# FD_Capacitance_Sensor_v10.net
KiCad netlist of a schematic drawn in EAGLE
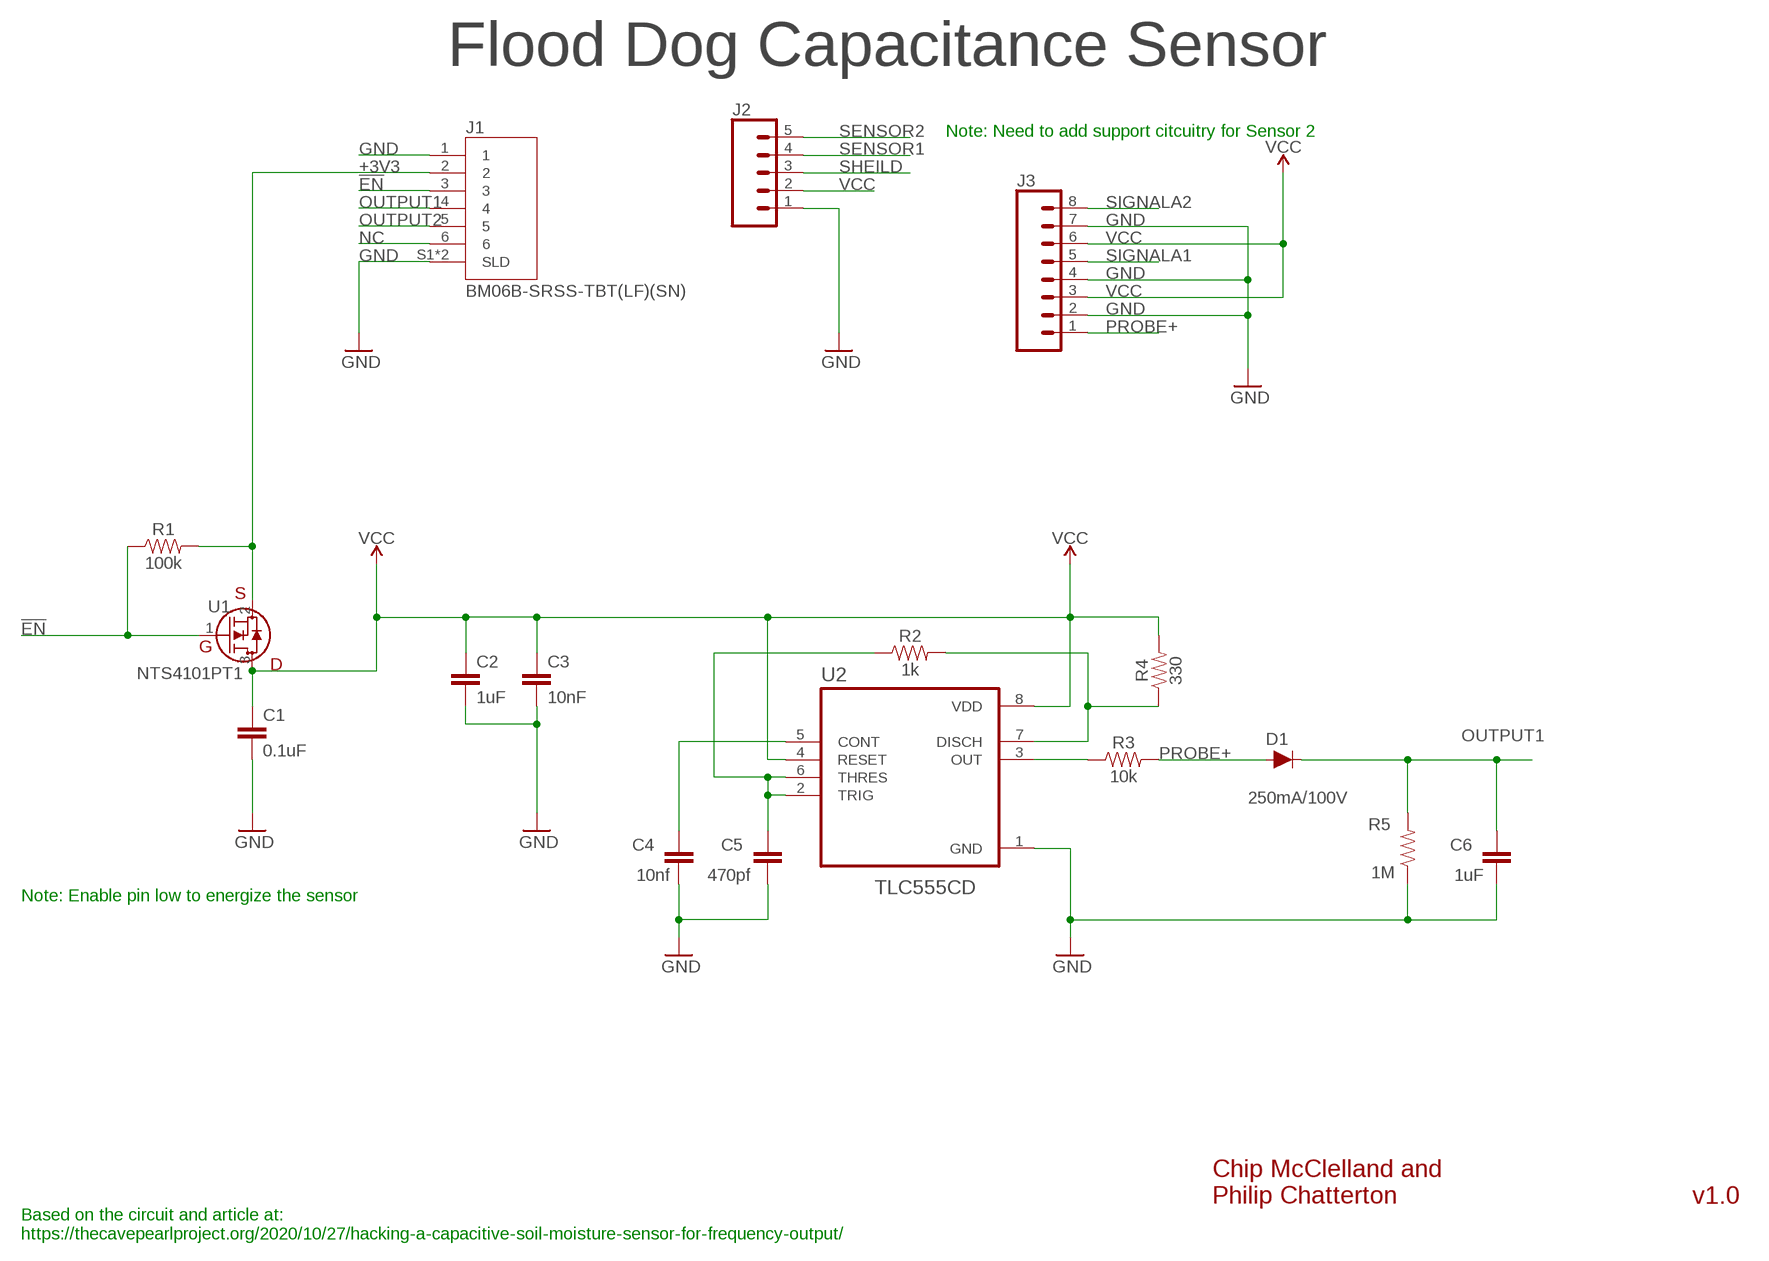
[diagram p0: schematic, sheet 1]

(export (version "E")
  (design (tool "Eeschema 10.0.6"))
  (components
    (comp (ref "C1")
      (value "0.1uF")
      (footprint "eagle-import:0805@1")
      (fields (field (name "HOUSEPART") "YES") (field (name "MPN") "MF-CAP-0805-0.1uF"))
      (libsource (lib "eagle-import") (part "CAP-MF-0.1UF-0805"))
    )
    (comp (ref "C2")
      (value "1uF")
      (footprint "eagle-import:0805@1")
      (fields (field (name "HOUSEPART") "yes") (field (name "MPN") "MF-CAP-0805-1uF"))
      (libsource (lib "eagle-import") (part "CAP-MF-1UF-0805"))
    )
    (comp (ref "C3")
      (value "10nF")
      (footprint "eagle-import:0805@1")
      (fields (field (name "HOUSEPART") "NO") (field (name "MPN") "C0805X103K1RAC3316"))
      (libsource (lib "eagle-import") (part "CAP-10NF-0805"))
    )
    (comp (ref "C4")
      (value "10nf")
      (footprint "eagle-import:C0805")
      (libsource (lib "eagle-import") (part "C-EUC0805"))
    )
    (comp (ref "C5")
      (value "470pf")
      (footprint "eagle-import:C0805")
      (libsource (lib "eagle-import") (part "C-EUC0805"))
    )
    (comp (ref "C6")
      (value "1uF")
      (footprint "eagle-import:C0805")
      (libsource (lib "eagle-import") (part "C-EUC0805"))
    )
    (comp (ref "D1")
      (value "250mA/100V")
      (footprint "eagle-import:SOD-323")
      (fields (field (name "MPN") "BAS16HT1G"))
      (libsource (lib "eagle-import") (part "DIODE-BAS16J"))
    )
    (comp (ref "J1")
      (value "BM06B-SRSS-TBT(LF)(SN)")
      (footprint "eagle-import:JST_BM06B-SRSS-TB(LF)(SN)")
      (libsource (lib "eagle-import") (part "BM06B-SRSS-TBT(LF)(SN)"))
    )
    (comp (ref "J2")
      (value "CONN_05SCREW")
      (footprint "eagle-import:SCREWTERMINAL-3.5MM-5")
      (libsource (lib "eagle-import") (part "CONN_05SCREW"))
    )
    (comp (ref "J3")
      (value "CONN_08\"")
      (footprint "eagle-import:1X08")
      (libsource (lib "eagle-import") (part "CONN_08{dblquote}"))
    )
    (comp (ref "R1")
      (value "100k")
      (footprint "eagle-import:0805")
      (fields (field (name "MPN") "MF-RES-0805-100K") (field (name "MPN_1") "MF-RES-0805-100K"))
      (libsource (lib "eagle-import") (part "RESISTOR-MF-100K-0805"))
    )
    (comp (ref "R2")
      (value "1k")
      (footprint "eagle-import:0805")
      (fields (field (name "HOUSEPART") "YES") (field (name "MPN") "MF-RES-0805-1K"))
      (libsource (lib "eagle-import") (part "RESISTOR-MF-1K-0805"))
    )
    (comp (ref "R3")
      (value "10k")
      (footprint "eagle-import:0805")
      (fields (field (name "MPN") "MF-RES-0805-10K"))
      (libsource (lib "eagle-import") (part "RESISTOR-MF-10K-0805"))
    )
    (comp (ref "R4")
      (value "330")
      (footprint "eagle-import:0805")
      (fields (field (name "HOUSEPART") "YES") (field (name "MPN") "MF-RES-0805-330"))
      (libsource (lib "eagle-import") (part "RESISTOR-MF-330-0805"))
    )
    (comp (ref "R5")
      (value "1M")
      (footprint "eagle-import:0805")
      (fields (field (name "HOUSEPART") "YES") (field (name "MPN") "MF-RES-0805-1K"))
      (libsource (lib "eagle-import") (part "RESISTOR-MF-1K-0805"))
    )
    (comp (ref "U1")
      (value "NTS4101PT1")
      (footprint "eagle-import:SOT_101PT1_ONS")
      (libsource (lib "eagle-import") (part "NTS4101PT1"))
    )
    (comp (ref "U2")
      (value "TLC555CD")
      (footprint "eagle-import:SOIC127P599X175-8N")
      (fields (field (name "DIGI-KEY_PART_NUMBER") "296-52992-ND") (field (name "MF") "Texas Instruments"))
      (libsource (lib "eagle-import") (part "TLC555CD"))
    )
  )
  (nets
    (net (code "1") (name "/+3V3") (class "Default")
      (node (ref "J1") (pin "2") (pinfunction "2_2") (pintype "passive"))
      (node (ref "R1") (pin "2") (pinfunction "2_2") (pintype "passive"))
      (node (ref "U1") (pin "2") (pinfunction "S_2") (pintype "passive"))
    )
    (net (code "2") (name "/NC") (class "Default")
      (node (ref "J1") (pin "6") (pinfunction "6_6") (pintype "passive"))
    )
    (net (code "3") (name "/OUTPUT1") (class "Default")
      (node (ref "C6") (pin "2") (pinfunction "2_2") (pintype "passive"))
      (node (ref "D1") (pin "C") (pinfunction "C_C") (pintype "passive"))
      (node (ref "J1") (pin "4") (pinfunction "4_4") (pintype "passive"))
      (node (ref "R5") (pin "2") (pinfunction "2_2") (pintype "passive"))
    )
    (net (code "4") (name "/OUTPUT2") (class "Default")
      (node (ref "J1") (pin "5") (pinfunction "5_5") (pintype "passive"))
    )
    (net (code "5") (name "/PROBE+") (class "Default")
      (node (ref "D1") (pin "A") (pinfunction "A_A") (pintype "passive"))
      (node (ref "J3") (pin "1") (pinfunction "1_1") (pintype "passive"))
      (node (ref "R3") (pin "2") (pinfunction "2_2") (pintype "passive"))
    )
    (net (code "6") (name "/SENSOR1") (class "Default")
      (node (ref "J2") (pin "4") (pinfunction "4_4") (pintype "passive"))
    )
    (net (code "7") (name "/SENSOR2") (class "Default")
      (node (ref "J2") (pin "5") (pinfunction "5_5") (pintype "passive"))
    )
    (net (code "8") (name "/SHEILD") (class "Default")
      (node (ref "J2") (pin "3") (pinfunction "3_3") (pintype "passive"))
    )
    (net (code "9") (name "/SIGNALA1") (class "Default")
      (node (ref "J3") (pin "5") (pinfunction "5_5") (pintype "passive"))
    )
    (net (code "10") (name "/SIGNALA2") (class "Default")
      (node (ref "J3") (pin "8") (pinfunction "8_8") (pintype "passive"))
    )
    (net (code "11") (name "/~{EN}") (class "Default")
      (node (ref "J1") (pin "3") (pinfunction "3_3") (pintype "passive"))
      (node (ref "R1") (pin "1") (pinfunction "1_1") (pintype "passive"))
      (node (ref "U1") (pin "1") (pinfunction "G_1") (pintype "passive"))
    )
    (net (code "12") (name "GND") (class "Default")
      (node (ref "C1") (pin "2") (pinfunction "2_2") (pintype "passive"))
      (node (ref "C2") (pin "2") (pinfunction "2_2") (pintype "passive"))
      (node (ref "C3") (pin "2") (pinfunction "2_2") (pintype "passive"))
      (node (ref "C4") (pin "1") (pinfunction "1_1") (pintype "passive"))
      (node (ref "C5") (pin "1") (pinfunction "1_1") (pintype "passive"))
      (node (ref "C6") (pin "1") (pinfunction "1_1") (pintype "passive"))
      (node (ref "J1") (pin "1") (pinfunction "1_1") (pintype "passive"))
      (node (ref "J1") (pin "S1") (pinfunction "SLD_S1") (pintype "passive"))
      (node (ref "J1") (pin "S2") (pinfunction "SLD_S2") (pintype "passive"))
      (node (ref "J2") (pin "1") (pinfunction "1_1") (pintype "passive"))
      (node (ref "J3") (pin "2") (pinfunction "2_2") (pintype "passive"))
      (node (ref "J3") (pin "4") (pinfunction "4_4") (pintype "passive"))
      (node (ref "J3") (pin "7") (pinfunction "7_7") (pintype "passive"))
      (node (ref "R5") (pin "1") (pinfunction "1_1") (pintype "passive"))
      (node (ref "U2") (pin "1") (pinfunction "GND_1") (pintype "power_in"))
    )
    (net (code "13") (name "Net-(U2-CONT)") (class "Default")
      (node (ref "C4") (pin "2") (pinfunction "2_2") (pintype "passive"))
      (node (ref "U2") (pin "5") (pinfunction "CONT_5") (pintype "input"))
    )
    (net (code "14") (name "Net-(U2-DISCH)") (class "Default")
      (node (ref "R2") (pin "2") (pinfunction "2_2") (pintype "passive"))
      (node (ref "R4") (pin "1") (pinfunction "1_1") (pintype "passive"))
      (node (ref "U2") (pin "7") (pinfunction "DISCH_7") (pintype "output"))
    )
    (net (code "15") (name "Net-(U2-OUT)") (class "Default")
      (node (ref "R3") (pin "1") (pinfunction "1_1") (pintype "passive"))
      (node (ref "U2") (pin "3") (pinfunction "OUT_3") (pintype "output"))
    )
    (net (code "16") (name "Net-(U2-THRES)") (class "Default")
      (node (ref "C5") (pin "2") (pinfunction "2_2") (pintype "passive"))
      (node (ref "R2") (pin "1") (pinfunction "1_1") (pintype "passive"))
      (node (ref "U2") (pin "2") (pinfunction "TRIG_2") (pintype "input"))
      (node (ref "U2") (pin "6") (pinfunction "THRES_6") (pintype "input"))
    )
    (net (code "17") (name "VCC") (class "Default")
      (node (ref "C1") (pin "1") (pinfunction "1_1") (pintype "passive"))
      (node (ref "C2") (pin "1") (pinfunction "1_1") (pintype "passive"))
      (node (ref "C3") (pin "1") (pinfunction "1_1") (pintype "passive"))
      (node (ref "J2") (pin "2") (pinfunction "2_2") (pintype "passive"))
      (node (ref "J3") (pin "3") (pinfunction "3_3") (pintype "passive"))
      (node (ref "J3") (pin "6") (pinfunction "6_6") (pintype "passive"))
      (node (ref "R4") (pin "2") (pinfunction "2_2") (pintype "passive"))
      (node (ref "U1") (pin "3") (pinfunction "D_3") (pintype "passive"))
      (node (ref "U2") (pin "4") (pinfunction "RESET_4") (pintype "input"))
      (node (ref "U2") (pin "8") (pinfunction "VDD_8") (pintype "power_in"))
    )
  )
)
